# SparkFun_ACS723_Breakout_v01.net
KiCad netlist of a schematic drawn in EAGLE
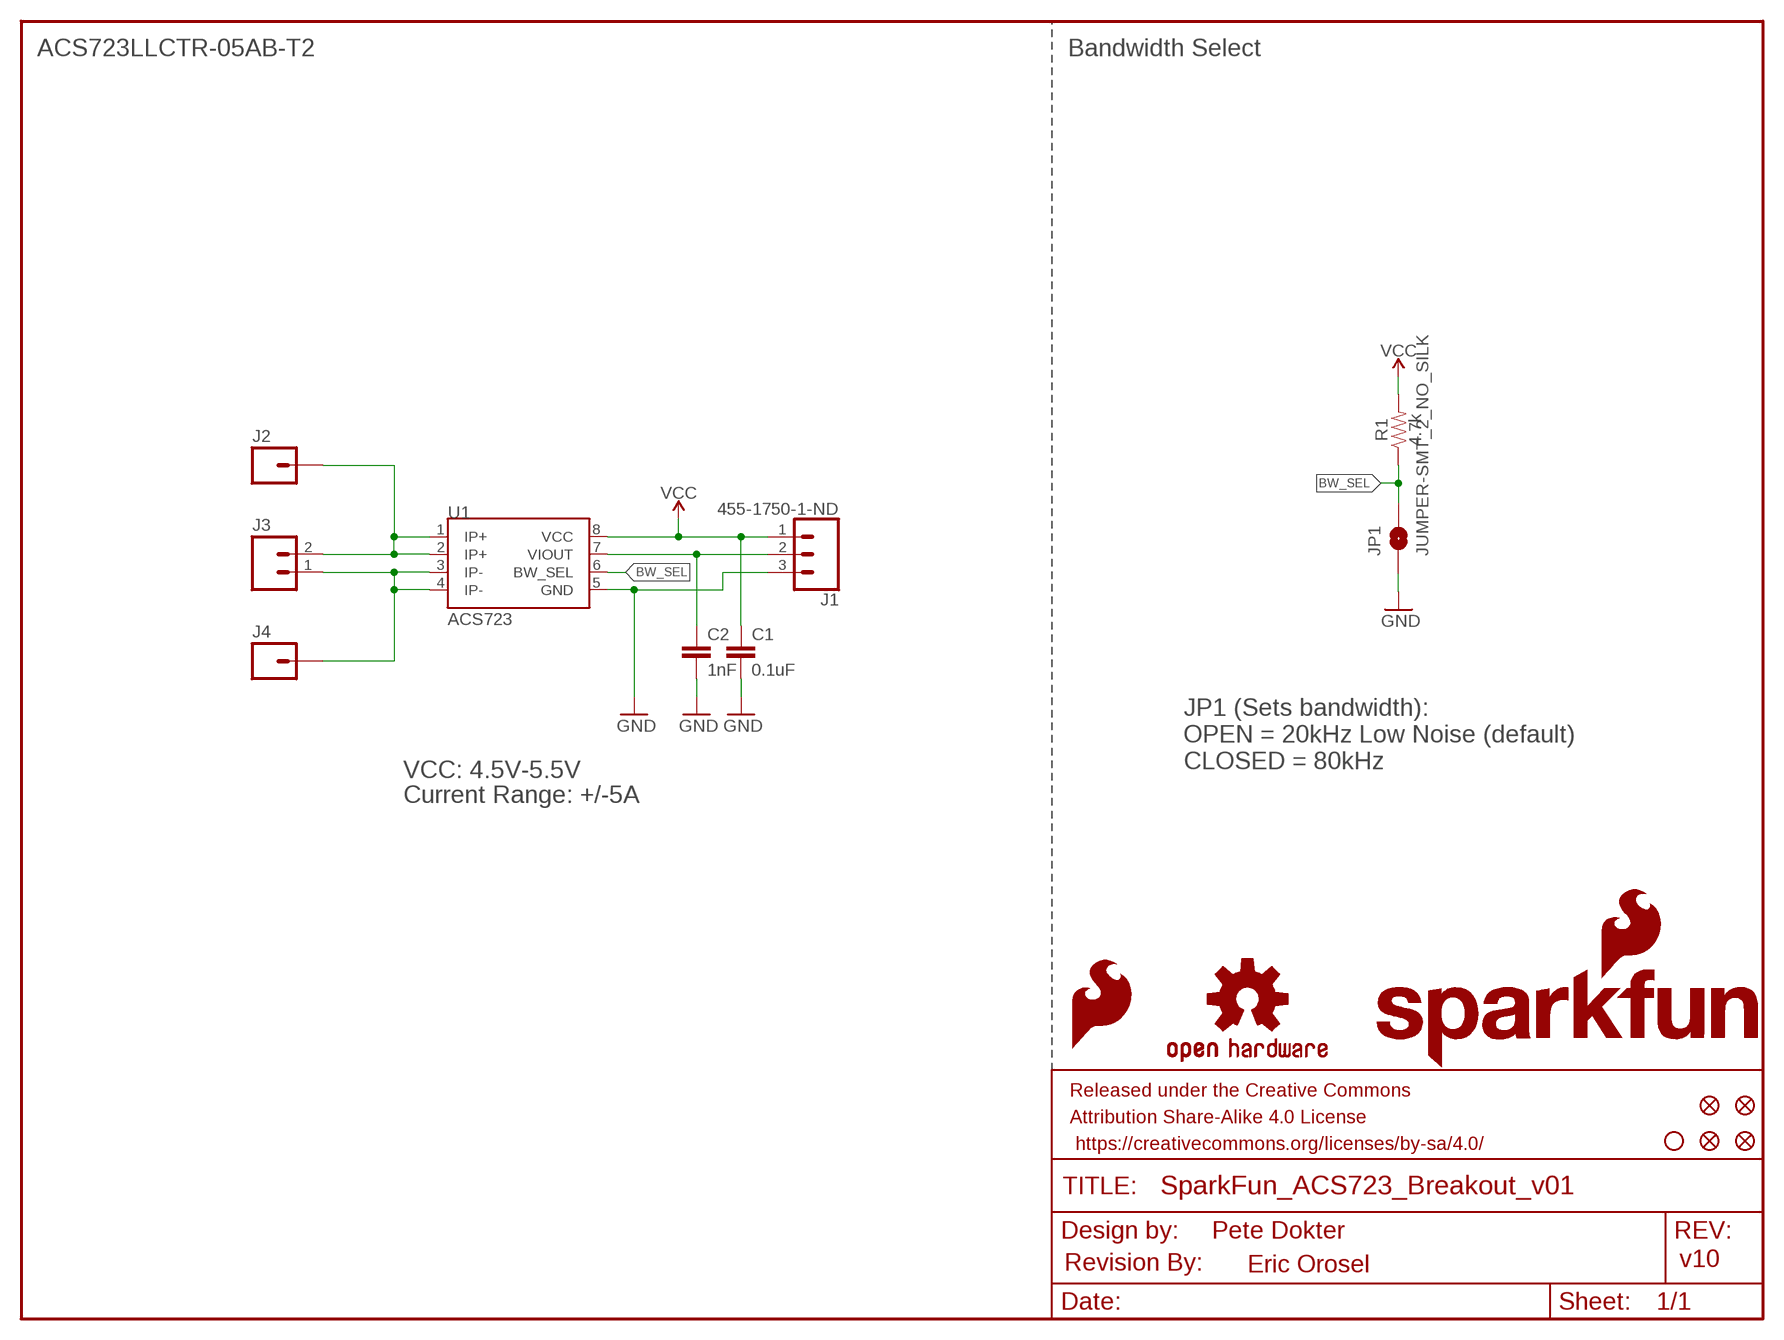
[diagram p0: schematic, sheet 1]

(export (version "E")
  (design (tool "Eeschema 10.0.6"))
  (components
    (comp (ref "C1")
      (value "0.1uF")
      (footprint "eagle-import:0603")
      (libsource (lib "eagle-import") (part "0.1UF-0603-25V-(+80/-20%)"))
    )
    (comp (ref "C2")
      (value "1nF")
      (footprint "eagle-import:0603")
      (libsource (lib "eagle-import") (part "1.0NF/1000PF-0603-50V-10%"))
    )
    (comp (ref "FD2")
      (value "FIDUCIAL1X2")
      (footprint "eagle-import:FIDUCIAL-1X2")
      (libsource (lib "eagle-import") (part "FIDUCIAL1X2"))
    )
    (comp (ref "FD3")
      (value "FIDUCIAL1X2")
      (footprint "eagle-import:FIDUCIAL-1X2")
      (libsource (lib "eagle-import") (part "FIDUCIAL1X2"))
    )
    (comp (ref "FD4")
      (value "FIDUCIAL1X2")
      (footprint "eagle-import:FIDUCIAL-1X2")
      (libsource (lib "eagle-import") (part "FIDUCIAL1X2"))
    )
    (comp (ref "FD5")
      (value "FIDUCIAL1X2")
      (footprint "eagle-import:FIDUCIAL-1X2")
      (libsource (lib "eagle-import") (part "FIDUCIAL1X2"))
    )
    (comp (ref "FRAME1")
      (value "FRAME-LETTER")
      (footprint "eagle-import:CREATIVE_COMMONS")
      (libsource (lib "eagle-import") (part "FRAME-LETTER"))
    )
    (comp (ref "J1")
      (value "455-1750-1-ND")
      (footprint "eagle-import:1X03")
      (libsource (lib "eagle-import") (part "CONN_03"))
    )
    (comp (ref "J2")
      (value "M01-SMTSO-256-ET")
      (footprint "eagle-import:SMTSO-256-ET")
      (libsource (lib "eagle-import") (part "M01-SMTSO-256-ET"))
    )
    (comp (ref "J3")
      (value "M021X02_NO_SILK")
      (footprint "eagle-import:1X02_NO_SILK@1")
      (libsource (lib "eagle-import") (part "M021X02_NO_SILK"))
    )
    (comp (ref "J4")
      (value "M01-SMTSO-256-ET")
      (footprint "eagle-import:SMTSO-256-ET")
      (libsource (lib "eagle-import") (part "M01-SMTSO-256-ET"))
    )
    (comp (ref "JP1")
      (value "JUMPER-SMT_2_NO_SILK")
      (footprint "eagle-import:SMT-JUMPER_2_NO_SILK")
      (libsource (lib "eagle-import") (part "JUMPER-SMT_2_NO_SILK"))
    )
    (comp (ref "JP3")
      (value "STAND-OFFTIGHT")
      (footprint "eagle-import:STAND-OFF-TIGHT")
      (libsource (lib "eagle-import") (part "STAND-OFFTIGHT"))
    )
    (comp (ref "LOGO1")
      (value "SFE_LOGO_FLAME.1_INCH")
      (footprint "eagle-import:SFE_LOGO_FLAME_.1")
      (libsource (lib "eagle-import") (part "SFE_LOGO_FLAME.1_INCH"))
    )
    (comp (ref "LOGO3")
      (value "SFE_LOGO_NAME_FLAME.1_INCH")
      (footprint "eagle-import:SFE_LOGO_NAME_FLAME_.1")
      (libsource (lib "eagle-import") (part "SFE_LOGO_NAME_FLAME.1_INCH"))
    )
    (comp (ref "LOGO4")
      (value "OSHW-LOGOM")
      (footprint "eagle-import:OSHW-LOGO-M")
      (libsource (lib "eagle-import") (part "OSHW-LOGOM"))
    )
    (comp (ref "R1")
      (value "4.7k")
      (footprint "eagle-import:0603")
      (libsource (lib "eagle-import") (part "4.7KOHM-0603-1/10W-1%"))
    )
    (comp (ref "U$1")
      (value "REVISION")
      (footprint "eagle-import:REVISION")
      (libsource (lib "eagle-import") (part "REVISION"))
    )
    (comp (ref "U1")
      (value "ACS723")
      (footprint "eagle-import:SO08")
      (fields (field (name "PART_#") "ACS723ACS723LLCTR-05AB-T2"))
      (libsource (lib "eagle-import") (part "ACS723"))
    )
  )
  (nets
    (net (code "1") (name "BW_SEL") (class "Default")
      (node (ref "JP1") (pin "2") (pinfunction "2_2") (pintype "passive"))
      (node (ref "R1") (pin "1") (pinfunction "1_1") (pintype "passive"))
      (node (ref "U1") (pin "6") (pinfunction "BW_SEL_6") (pintype "bidirectional"))
    )
    (net (code "2") (name "GND") (class "Default")
      (node (ref "C1") (pin "2") (pinfunction "2_2") (pintype "passive"))
      (node (ref "C2") (pin "2") (pinfunction "2_2") (pintype "passive"))
      (node (ref "J1") (pin "3") (pinfunction "3_3") (pintype "passive"))
      (node (ref "JP1") (pin "1") (pinfunction "1_1") (pintype "passive"))
      (node (ref "U1") (pin "5") (pinfunction "GND_5") (pintype "bidirectional"))
    )
    (net (code "3") (name "Net-(J2-1)") (class "Default")
      (node (ref "J2") (pin "P$1") (pinfunction "1_P$1") (pintype "passive"))
      (node (ref "J3") (pin "2") (pinfunction "2_2") (pintype "passive"))
      (node (ref "U1") (pin "1") (pinfunction "IP+_1") (pintype "input"))
      (node (ref "U1") (pin "2") (pinfunction "IP+_2") (pintype "input"))
    )
    (net (code "4") (name "Net-(J4-1)") (class "Default")
      (node (ref "J3") (pin "1") (pinfunction "1_1") (pintype "passive"))
      (node (ref "J4") (pin "P$1") (pinfunction "1_P$1") (pintype "passive"))
      (node (ref "U1") (pin "3") (pinfunction "IP-_3") (pintype "bidirectional"))
      (node (ref "U1") (pin "4") (pinfunction "IP-_4") (pintype "bidirectional"))
    )
    (net (code "5") (name "Net-(U1-VIOUT)") (class "Default")
      (node (ref "C2") (pin "1") (pinfunction "1_1") (pintype "passive"))
      (node (ref "J1") (pin "2") (pinfunction "2_2") (pintype "passive"))
      (node (ref "U1") (pin "7") (pinfunction "VIOUT_7") (pintype "bidirectional"))
    )
    (net (code "6") (name "VCC") (class "Default")
      (node (ref "C1") (pin "1") (pinfunction "1_1") (pintype "passive"))
      (node (ref "J1") (pin "1") (pinfunction "1_1") (pintype "passive"))
      (node (ref "R1") (pin "2") (pinfunction "2_2") (pintype "passive"))
      (node (ref "U1") (pin "8") (pinfunction "VCC_8") (pintype "bidirectional"))
    )
  )
)
